# Analog.net
KiCad netlist of a schematic drawn in Altium Designer
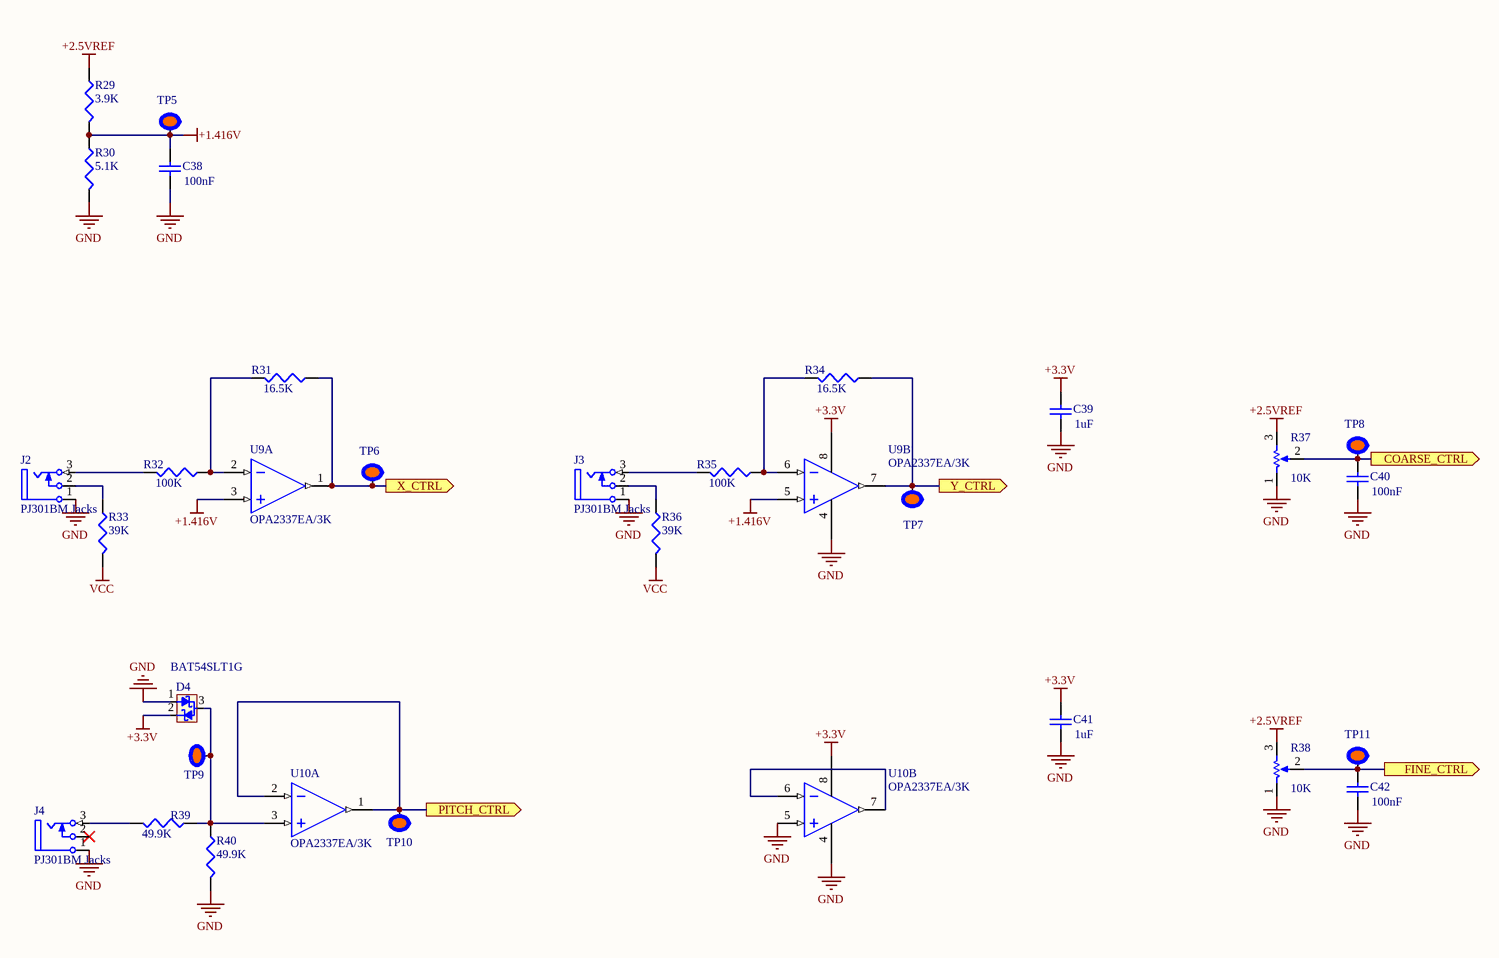
[diagram p0: Analog.SchDoc]

(export (version "E")
  (design (tool "Eeschema 10.0.6"))
  (components
    (comp (ref "C38")
      (value "100nF")
      (footprint "RES_0603")
      (description "Capacitor")
      (fields
        (field (name "MANUFACTURER") "AVX Corporation")
        (field (name "MANUFACTURER PART NUMBER") "06035G104ZAT2A")
      )
      (libsource (lib "Miscellaneous Devices") (part "Cap"))
    )
    (comp (ref "C39")
      (value "1uF")
      (footprint "RES_0603")
      (description "Capacitor")
      (fields
        (field (name "MANUFACTURER") "Samsung Electro-Mechanics")
        (field (name "MANUFACTURER PART NUMBER") "CL10A105KA8NNNC")
      )
      (libsource (lib "Miscellaneous Devices") (part "Cap"))
    )
    (comp (ref "C40")
      (value "100nF")
      (footprint "RES_0603")
      (description "Capacitor")
      (fields
        (field (name "MANUFACTURER") "AVX Corporation")
        (field (name "MANUFACTURER PART NUMBER") "06035G104ZAT2A")
      )
      (libsource (lib "Miscellaneous Devices") (part "Cap"))
    )
    (comp (ref "C41")
      (value "1uF")
      (footprint "RES_0603")
      (description "Capacitor")
      (fields
        (field (name "MANUFACTURER") "Samsung Electro-Mechanics")
        (field (name "MANUFACTURER PART NUMBER") "CL10A105KA8NNNC")
      )
      (libsource (lib "Miscellaneous Devices") (part "Cap"))
    )
    (comp (ref "C42")
      (value "100nF")
      (footprint "RES_0603")
      (description "Capacitor")
      (fields
        (field (name "MANUFACTURER") "AVX Corporation")
        (field (name "MANUFACTURER PART NUMBER") "06035G104ZAT2A")
      )
      (libsource (lib "Miscellaneous Devices") (part "Cap"))
    )
    (comp (ref "D4")
      (value "BAT54SLT1G")
      (footprint "SOT23")
      (description "DIODE ARRAY SCHOTTKY")
      (fields
        (field (name "MANUFACTURER") "ON Semiconductor")
        (field (name "MANUFACTURER PART NUMBER") "BAT54SLT1G")
      )
      (libsource (lib "Custom") (part "SCHOTTKY DIODE ARRAY"))
    )
    (comp (ref "J2")
      (value "PJ301BM Jacks")
      (footprint "WQP-PJ301M-12_JACK")
      (description "Jack Socket, 1/4\" [6.5mm], Thru-Hole, Vertical, 2-Conductor with Tip closed")
      (fields (field (name "MANUFACTURER") "Thonkiconn"))
      (libsource (lib "Miscellaneous Connectors") (part "Phonejack2 TN"))
    )
    (comp (ref "J3")
      (value "PJ301BM Jacks")
      (footprint "WQP-PJ301M-12_JACK")
      (description "Jack Socket, 1/4\" [6.5mm], Thru-Hole, Vertical, 2-Conductor with Tip closed")
      (fields (field (name "MANUFACTURER") "Thonkiconn"))
      (libsource (lib "Miscellaneous Connectors") (part "Phonejack2 TN"))
    )
    (comp (ref "J4")
      (value "PJ301BM Jacks")
      (footprint "WQP-PJ301M-12_JACK")
      (description "Jack Socket, 1/4\" [6.5mm], Thru-Hole, Vertical, 2-Conductor with Tip closed")
      (fields (field (name "MANUFACTURER") "Thonkiconn"))
      (libsource (lib "Miscellaneous Connectors") (part "Phonejack2 TN"))
    )
    (comp (ref "R29")
      (value "3.9K")
      (footprint "RES_0603")
      (description "Resistor")
      (fields
        (field (name "MANUFACTURER") "Panasonic")
        (field (name "MANUFACTURER PART NUMBER") "ERA-3AEB392V")
      )
      (libsource (lib "Miscellaneous Devices") (part "Res3"))
    )
    (comp (ref "R30")
      (value "5.1K")
      (footprint "RES_0603")
      (description "Resistor")
      (fields
        (field (name "MANUFACTURER") "Panasonic")
        (field (name "MANUFACTURER PART NUMBER") "ERA-3AEB512V")
      )
      (libsource (lib "Miscellaneous Devices") (part "Res3"))
    )
    (comp (ref "R31")
      (value "16.5K")
      (footprint "RES_0603")
      (description "Resistor")
      (fields
        (field (name "MANUFACTURER") "Panasonic")
        (field (name "MANUFACTURER PART NUMBER") "ERA-3AEB1652V")
      )
      (libsource (lib "Miscellaneous Devices") (part "Res3"))
    )
    (comp (ref "R32")
      (value "100K")
      (footprint "RES_0603")
      (description "Resistor")
      (fields
        (field (name "MANUFACTURER") "Susumu")
        (field (name "MANUFACTURER PART NUMBER") "RR0816P-104-D")
      )
      (libsource (lib "Miscellaneous Devices") (part "Res3"))
    )
    (comp (ref "R33")
      (value "39K")
      (footprint "RES_0603")
      (description "ERA-3AEB393V")
      (fields (field (name "MANUFACTURER") "Panasonic Electronic Components"))
      (libsource (lib "Miscellaneous Devices") (part "Res3"))
    )
    (comp (ref "R34")
      (value "16.5K")
      (footprint "RES_0603")
      (description "Resistor")
      (fields
        (field (name "MANUFACTURER") "Panasonic")
        (field (name "MANUFACTURER PART NUMBER") "ERA-3AEB1652V")
      )
      (libsource (lib "Miscellaneous Devices") (part "Res3"))
    )
    (comp (ref "R35")
      (value "100K")
      (footprint "RES_0603")
      (description "Resistor")
      (fields
        (field (name "MANUFACTURER") "Susumu")
        (field (name "MANUFACTURER PART NUMBER") "RR0816P-104-D")
      )
      (libsource (lib "Miscellaneous Devices") (part "Res3"))
    )
    (comp (ref "R36")
      (value "39K")
      (footprint "RES_0603")
      (description "ERA-3AEB393V")
      (fields (field (name "MANUFACTURER") "Panasonic Electronic Components"))
      (libsource (lib "Miscellaneous Devices") (part "Res3"))
    )
    (comp (ref "R37")
      (value "10K")
      (footprint "P0915NEC15BR100K")
      (description "Potentiometer")
      (fields
        (field (name "MANUFACTURER") "TT Electronics/BI")
        (field (name "MANUFACTURER PART NUMBER") "P0915N-FC15BR10K")
      )
      (libsource (lib "Custom") (part "RPot"))
    )
    (comp (ref "R38")
      (value "10K")
      (footprint "P0915NEC15BR100K")
      (description "Potentiometer")
      (fields
        (field (name "MANUFACTURER") "TT Electronics/BI")
        (field (name "MANUFACTURER PART NUMBER") "P0915N-FC15BR10K")
      )
      (libsource (lib "Custom") (part "RPot"))
    )
    (comp (ref "R39")
      (value "49.9K")
      (footprint "RES_0603")
      (description "Resistor")
      (fields
        (field (name "MANUFACTURER") "Panasonic")
        (field (name "MANUFACTURER PART NUMBER") "ERA-3AEB4992V")
      )
      (libsource (lib "Miscellaneous Devices") (part "Res3"))
    )
    (comp (ref "R40")
      (value "49.9K")
      (footprint "RES_0603")
      (description "Resistor")
      (fields
        (field (name "MANUFACTURER") "Panasonic")
        (field (name "MANUFACTURER PART NUMBER") "ERA-3AEB4992V")
      )
      (libsource (lib "Miscellaneous Devices") (part "Res3"))
    )
    (comp (ref "TP5")
      (value "loop test point")
      (footprint "Test Point Mt Hole")
      (description "Test Point Loop Miniature Keysone")
      (fields
        (field (name "MANUFACTURER") "Keystone Electronics")
        (field (name "MANUFACTURER PART NUMBER") "5003")
      )
      (libsource (lib "Custom") (part "Test Point"))
    )
    (comp (ref "TP6")
      (value "loop test point")
      (footprint "Test Point Mt Hole")
      (description "Test Point Loop Miniature Keysone")
      (fields
        (field (name "MANUFACTURER") "Keystone Electronics")
        (field (name "MANUFACTURER PART NUMBER") "5003")
      )
      (libsource (lib "Custom") (part "Test Point"))
    )
    (comp (ref "TP7")
      (value "loop test point")
      (footprint "Test Point Mt Hole")
      (description "Test Point Loop Miniature Keysone")
      (fields
        (field (name "MANUFACTURER") "Keystone Electronics")
        (field (name "MANUFACTURER PART NUMBER") "5003")
      )
      (libsource (lib "Custom") (part "Test Point"))
    )
    (comp (ref "TP8")
      (value "loop test point")
      (footprint "Test Point Mt Hole")
      (description "Test Point Loop Miniature Keysone")
      (fields
        (field (name "MANUFACTURER") "Keystone Electronics")
        (field (name "MANUFACTURER PART NUMBER") "5003")
      )
      (libsource (lib "Custom") (part "Test Point"))
    )
    (comp (ref "TP9")
      (value "loop test point")
      (footprint "Test Point Mt Hole")
      (description "Test Point Loop Miniature Keysone")
      (fields
        (field (name "MANUFACTURER") "Keystone Electronics")
        (field (name "MANUFACTURER PART NUMBER") "5003")
      )
      (libsource (lib "Custom") (part "Test Point"))
    )
    (comp (ref "TP10")
      (value "loop test point")
      (footprint "Test Point Mt Hole")
      (description "Test Point Loop Miniature Keysone")
      (fields
        (field (name "MANUFACTURER") "Keystone Electronics")
        (field (name "MANUFACTURER PART NUMBER") "5003")
      )
      (libsource (lib "Custom") (part "Test Point"))
    )
    (comp (ref "TP11")
      (value "loop test point")
      (footprint "Test Point Mt Hole")
      (description "Test Point Loop Miniature Keysone")
      (fields
        (field (name "MANUFACTURER") "Keystone Electronics")
        (field (name "MANUFACTURER PART NUMBER") "5003")
      )
      (libsource (lib "Custom") (part "Test Point"))
    )
    (comp (ref "U9")
      (value "OPA2337EA/3K")
      (footprint "SOT-23-8")
      (fields (field (name "MANUFACTURER") "Texas Instruments"))
      (libsource (lib "Custom") (part "OPA2137E/2K5"))
    )
    (comp (ref "U10")
      (value "OPA2337EA/3K")
      (footprint "SOT-23-8")
      (fields (field (name "MANUFACTURER") "Texas Instruments"))
      (libsource (lib "Custom") (part "OPA2137E/2K5"))
    )
  )
  (nets
    (net (code "1") (name "+1.416V") (class "Default")
      (node (ref "C38") (pin "2") (pinfunction "2_2") (pintype "passive"))
      (node (ref "R29") (pin "2") (pinfunction "2_2") (pintype "passive"))
      (node (ref "R30") (pin "1") (pinfunction "1_1") (pintype "passive"))
      (node (ref "TP5") (pin "1") (pinfunction "1_1") (pintype "passive"))
      (node (ref "U9") (pin "3") (pinfunction "IN_A+_3") (pintype "input"))
      (node (ref "U9") (pin "5") (pinfunction "IN_B+_5") (pintype "input"))
    )
    (net (code "2") (name "+2.5VREF") (class "Default")
      (node (ref "R29") (pin "1") (pinfunction "1_1") (pintype "passive"))
      (node (ref "R37") (pin "3") (pinfunction "3_3") (pintype "passive"))
      (node (ref "R38") (pin "3") (pinfunction "3_3") (pintype "passive"))
    )
    (net (code "3") (name "+3.3V") (class "Default")
      (node (ref "C39") (pin "2") (pinfunction "2_2") (pintype "passive"))
      (node (ref "C41") (pin "2") (pinfunction "2_2") (pintype "passive"))
      (node (ref "D4") (pin "2") (pinfunction "2_2") (pintype "passive"))
      (node (ref "U10") (pin "8") (pinfunction "8_8") (pintype "passive"))
      (node (ref "U9") (pin "8") (pinfunction "8_8") (pintype "passive"))
    )
    (net (code "4") (name "/COARSE_CTRL") (class "Default")
      (node (ref "C40") (pin "2") (pinfunction "2_2") (pintype "passive"))
      (node (ref "R37") (pin "2") (pinfunction "2_2") (pintype "passive"))
      (node (ref "TP8") (pin "1") (pinfunction "1_1") (pintype "passive"))
    )
    (net (code "5") (name "/FINE_CTRL") (class "Default")
      (node (ref "C42") (pin "2") (pinfunction "2_2") (pintype "passive"))
      (node (ref "R38") (pin "2") (pinfunction "2_2") (pintype "passive"))
      (node (ref "TP11") (pin "1") (pinfunction "1_1") (pintype "passive"))
    )
    (net (code "6") (name "/PITCH_CTRL") (class "Default")
      (node (ref "TP10") (pin "1") (pinfunction "1_1") (pintype "passive"))
      (node (ref "U10") (pin "1") (pinfunction "OUT_A_1") (pintype "output"))
      (node (ref "U10") (pin "2") (pinfunction "IN_A-_2") (pintype "input"))
    )
    (net (code "7") (name "/X_CTRL") (class "Default")
      (node (ref "R31") (pin "1") (pinfunction "1_1") (pintype "passive"))
      (node (ref "TP6") (pin "1") (pinfunction "1_1") (pintype "passive"))
      (node (ref "U9") (pin "1") (pinfunction "OUT_A_1") (pintype "output"))
    )
    (net (code "8") (name "/Y_CTRL") (class "Default")
      (node (ref "R34") (pin "1") (pinfunction "1_1") (pintype "passive"))
      (node (ref "TP7") (pin "1") (pinfunction "1_1") (pintype "passive"))
      (node (ref "U9") (pin "7") (pinfunction "OUT_B_7") (pintype "output"))
    )
    (net (code "9") (name "GND") (class "Default")
      (node (ref "C38") (pin "1") (pinfunction "1_1") (pintype "passive"))
      (node (ref "C39") (pin "1") (pinfunction "1_1") (pintype "passive"))
      (node (ref "C40") (pin "1") (pinfunction "1_1") (pintype "passive"))
      (node (ref "C41") (pin "1") (pinfunction "1_1") (pintype "passive"))
      (node (ref "C42") (pin "1") (pinfunction "1_1") (pintype "passive"))
      (node (ref "D4") (pin "1") (pinfunction "1_1") (pintype "passive"))
      (node (ref "J2") (pin "1") (pinfunction "S_1") (pintype "power_in"))
      (node (ref "J3") (pin "1") (pinfunction "S_1") (pintype "power_in"))
      (node (ref "J4") (pin "1") (pinfunction "S_1") (pintype "power_in"))
      (node (ref "R30") (pin "2") (pinfunction "2_2") (pintype "passive"))
      (node (ref "R37") (pin "1") (pinfunction "1_1") (pintype "passive"))
      (node (ref "R38") (pin "1") (pinfunction "1_1") (pintype "passive"))
      (node (ref "R40") (pin "2") (pinfunction "2_2") (pintype "passive"))
      (node (ref "U10") (pin "4") (pinfunction "4_4") (pintype "passive"))
      (node (ref "U10") (pin "5") (pinfunction "IN_B+_5") (pintype "input"))
      (node (ref "U9") (pin "4") (pinfunction "4_4") (pintype "passive"))
    )
    (net (code "10") (name "Net-(J2-T)") (class "Default")
      (node (ref "J2") (pin "3") (pinfunction "T_3") (pintype "input"))
      (node (ref "R32") (pin "2") (pinfunction "2_2") (pintype "passive"))
    )
    (net (code "11") (name "Net-(J2-TN)") (class "Default")
      (node (ref "J2") (pin "2") (pinfunction "TN_2") (pintype "passive"))
      (node (ref "R33") (pin "1") (pinfunction "1_1") (pintype "passive"))
    )
    (net (code "12") (name "Net-(J3-T)") (class "Default")
      (node (ref "J3") (pin "3") (pinfunction "T_3") (pintype "input"))
      (node (ref "R35") (pin "2") (pinfunction "2_2") (pintype "passive"))
    )
    (net (code "13") (name "Net-(J3-TN)") (class "Default")
      (node (ref "J3") (pin "2") (pinfunction "TN_2") (pintype "passive"))
      (node (ref "R36") (pin "1") (pinfunction "1_1") (pintype "passive"))
    )
    (net (code "14") (name "Net-(J4-T)") (class "Default")
      (node (ref "J4") (pin "3") (pinfunction "T_3") (pintype "input"))
      (node (ref "R39") (pin "2") (pinfunction "2_2") (pintype "passive"))
    )
    (net (code "15") (name "Net-(U9A-IN_A-)") (class "Default")
      (node (ref "R31") (pin "2") (pinfunction "2_2") (pintype "passive"))
      (node (ref "R32") (pin "1") (pinfunction "1_1") (pintype "passive"))
      (node (ref "U9") (pin "2") (pinfunction "IN_A-_2") (pintype "input"))
    )
    (net (code "16") (name "Net-(U9B-IN_B-)") (class "Default")
      (node (ref "R34") (pin "2") (pinfunction "2_2") (pintype "passive"))
      (node (ref "R35") (pin "1") (pinfunction "1_1") (pintype "passive"))
      (node (ref "U9") (pin "6") (pinfunction "IN_B-_6") (pintype "input"))
    )
    (net (code "17") (name "Net-(U10A-IN_A+)") (class "Default")
      (node (ref "D4") (pin "3") (pinfunction "3_3") (pintype "passive"))
      (node (ref "R39") (pin "1") (pinfunction "1_1") (pintype "passive"))
      (node (ref "R40") (pin "1") (pinfunction "1_1") (pintype "passive"))
      (node (ref "TP9") (pin "1") (pinfunction "1_1") (pintype "passive"))
      (node (ref "U10") (pin "3") (pinfunction "IN_A+_3") (pintype "input"))
    )
    (net (code "18") (name "Net-(U10B-IN_B-)") (class "Default")
      (node (ref "U10") (pin "6") (pinfunction "IN_B-_6") (pintype "input"))
      (node (ref "U10") (pin "7") (pinfunction "OUT_B_7") (pintype "output"))
    )
    (net (code "19") (name "VCC") (class "Default")
      (node (ref "R33") (pin "2") (pinfunction "2_2") (pintype "passive"))
      (node (ref "R36") (pin "2") (pinfunction "2_2") (pintype "passive"))
    )
    (net (code "20") (name "unconnected-(J4-TN-Pad2)") (class "Default")
      (node (ref "J4") (pin "2") (pinfunction "TN_2") (pintype "passive+no_connect"))
    )
  )
)
